# Ethernet1.net
KiCad netlist of a schematic drawn in Altium Designer
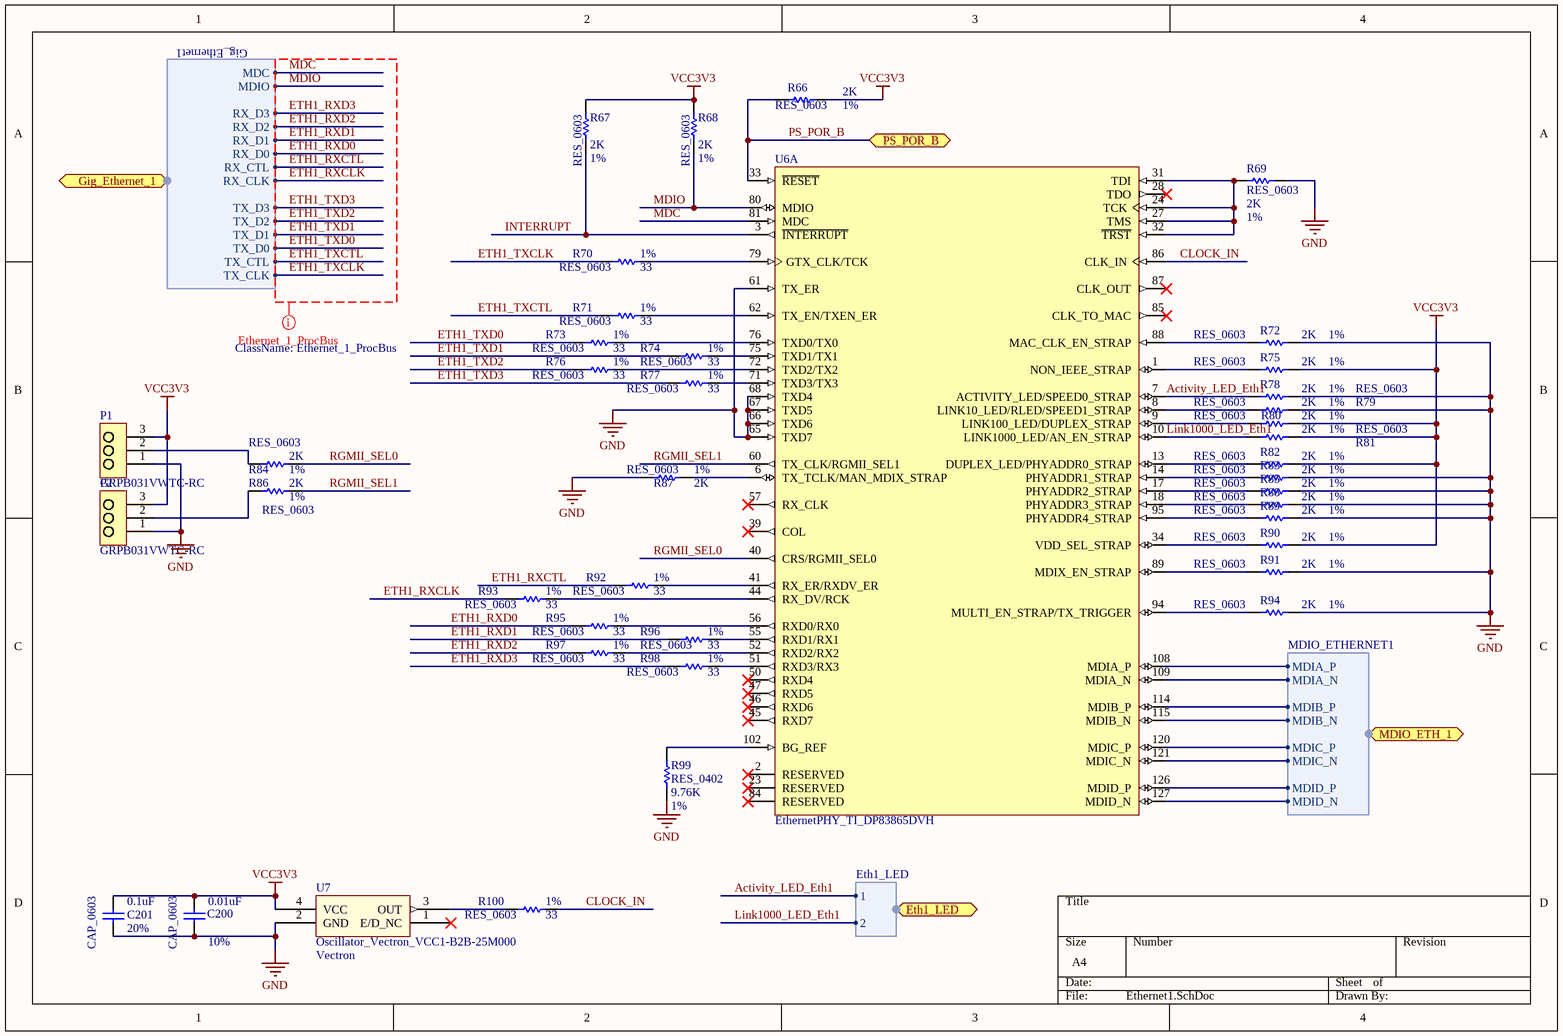
[diagram p0: Ethernet1.SchDoc]

(export (version "E")
  (design (tool "Eeschema 10.0.6"))
  (components
    (comp (ref "C200")
      (value "CAP_0603")
      (footprint "CAPC0603(1608)100_N")
      (description "CAP CER 10000PF 6.3V X7R 0603")
      (fields
        (field (name "ALTIUM_VALUE") "0.01uF")
        (field (name "TOLERANCE") "10%")
        (field (name "PART NUMBER") "C0603C103K9RACTU")
        (field (name "MANUFACTURER") "Kemet")
      )
      (libsource (lib "COMRAD_Database") (part "CAP_0603"))
    )
    (comp (ref "C201")
      (value "CAP_0603")
      (footprint "CAPC0603(1608)100_N")
      (description "CAP CER 0.1UF 6.3V 20% X7R 0603")
      (fields
        (field (name "ALTIUM_VALUE") "0.1uF")
        (field (name "TOLERANCE") "20%")
        (field (name "PART NUMBER") "6R3X14W104MV4T")
        (field (name "MANUFACTURER") "Johanson Dielectrics Inc")
      )
      (libsource (lib "COMRAD_Database") (part "CAP_0603"))
    )
    (comp (ref "P1")
      (value "GRPB031VWTC-RC")
      (footprint "Header_3-Pos_Sullins_GRPB031VWTC-RC")
      (description "CONN HEADER .050\" 3POS SMD GOLD")
      (fields (field (name "MANUFACTURER") "Sullins Connector Solutions"))
      (libsource (lib "COMRAD_Database") (part "Jumper_Header3"))
    )
    (comp (ref "P2")
      (value "GRPB031VWTC-RC")
      (footprint "Header_3-Pos_Sullins_GRPB031VWTC-RC")
      (description "CONN HEADER .050\" 3POS SMD GOLD")
      (fields (field (name "MANUFACTURER") "Sullins Connector Solutions"))
      (libsource (lib "COMRAD_Database") (part "Jumper_Header3"))
    )
    (comp (ref "R66")
      (value "RES_0603")
      (footprint "RESC0603(1608)_N")
      (description "RES 2.00K OHM 1/10W 1% 0603 SMD")
      (fields
        (field (name "ALTIUM_VALUE") "2K")
        (field (name "TOLERANCE") "1%")
        (field (name "PART NUMBER") "ERJ-3EKF2001V")
        (field (name "MANUFACTURER") "Panasonic Electronics Components")
      )
      (libsource (lib "COMRAD_Database") (part "RES_0603"))
    )
    (comp (ref "R67")
      (value "RES_0603")
      (footprint "RESC0603(1608)_N")
      (description "RES 2.00K OHM 1/10W 1% 0603 SMD")
      (fields
        (field (name "ALTIUM_VALUE") "2K")
        (field (name "TOLERANCE") "1%")
        (field (name "PART NUMBER") "ERJ-3EKF2001V")
        (field (name "MANUFACTURER") "Panasonic Electronics Components")
      )
      (libsource (lib "COMRAD_Database") (part "RES_0603"))
    )
    (comp (ref "R68")
      (value "RES_0603")
      (footprint "RESC0603(1608)_N")
      (description "RES 2.00K OHM 1/10W 1% 0603 SMD")
      (fields
        (field (name "ALTIUM_VALUE") "2K")
        (field (name "TOLERANCE") "1%")
        (field (name "PART NUMBER") "ERJ-3EKF2001V")
        (field (name "MANUFACTURER") "Panasonic Electronics Components")
      )
      (libsource (lib "COMRAD_Database") (part "RES_0603"))
    )
    (comp (ref "R69")
      (value "RES_0603")
      (footprint "RESC0603(1608)_N")
      (description "RES 2.00K OHM 1/10W 1% 0603 SMD")
      (fields
        (field (name "ALTIUM_VALUE") "2K")
        (field (name "TOLERANCE") "1%")
        (field (name "PART NUMBER") "ERJ-3EKF2001V")
        (field (name "MANUFACTURER") "Panasonic Electronics Components")
      )
      (libsource (lib "COMRAD_Database") (part "RES_0603"))
    )
    (comp (ref "R70")
      (value "RES_0603")
      (footprint "RESC0603(1608)_N")
      (description "RES 33.0 OHM 1/10W 1% 0603 SMD")
      (fields
        (field (name "ALTIUM_VALUE") "33")
        (field (name "TOLERANCE") "1%")
        (field (name "PART NUMBER") "ERJ-3EKF33R0V")
        (field (name "MANUFACTURER") "Panasonic Electronics Components")
      )
      (libsource (lib "COMRAD_Database") (part "RES_0603"))
    )
    (comp (ref "R71")
      (value "RES_0603")
      (footprint "RESC0603(1608)_N")
      (description "RES 33.0 OHM 1/10W 1% 0603 SMD")
      (fields
        (field (name "ALTIUM_VALUE") "33")
        (field (name "TOLERANCE") "1%")
        (field (name "PART NUMBER") "ERJ-3EKF33R0V")
        (field (name "MANUFACTURER") "Panasonic Electronics Components")
      )
      (libsource (lib "COMRAD_Database") (part "RES_0603"))
    )
    (comp (ref "R72")
      (value "RES_0603")
      (footprint "RESC0603(1608)_N")
      (description "RES 2.00K OHM 1/10W 1% 0603 SMD")
      (fields
        (field (name "ALTIUM_VALUE") "2K")
        (field (name "TOLERANCE") "1%")
        (field (name "PART NUMBER") "ERJ-3EKF2001V")
        (field (name "MANUFACTURER") "Panasonic Electronics Components")
      )
      (libsource (lib "COMRAD_Database") (part "RES_0603"))
    )
    (comp (ref "R73")
      (value "RES_0603")
      (footprint "RESC0603(1608)_N")
      (description "RES 33.0 OHM 1/10W 1% 0603 SMD")
      (fields
        (field (name "ALTIUM_VALUE") "33")
        (field (name "TOLERANCE") "1%")
        (field (name "PART NUMBER") "ERJ-3EKF33R0V")
        (field (name "MANUFACTURER") "Panasonic Electronics Components")
      )
      (libsource (lib "COMRAD_Database") (part "RES_0603"))
    )
    (comp (ref "R74")
      (value "RES_0603")
      (footprint "RESC0603(1608)_N")
      (description "RES 33.0 OHM 1/10W 1% 0603 SMD")
      (fields
        (field (name "ALTIUM_VALUE") "33")
        (field (name "TOLERANCE") "1%")
        (field (name "PART NUMBER") "ERJ-3EKF33R0V")
        (field (name "MANUFACTURER") "Panasonic Electronics Components")
      )
      (libsource (lib "COMRAD_Database") (part "RES_0603"))
    )
    (comp (ref "R75")
      (value "RES_0603")
      (footprint "RESC0603(1608)_N")
      (description "RES 2.00K OHM 1/10W 1% 0603 SMD")
      (fields
        (field (name "ALTIUM_VALUE") "2K")
        (field (name "TOLERANCE") "1%")
        (field (name "PART NUMBER") "ERJ-3EKF2001V")
        (field (name "MANUFACTURER") "Panasonic Electronics Components")
      )
      (libsource (lib "COMRAD_Database") (part "RES_0603"))
    )
    (comp (ref "R76")
      (value "RES_0603")
      (footprint "RESC0603(1608)_N")
      (description "RES 33.0 OHM 1/10W 1% 0603 SMD")
      (fields
        (field (name "ALTIUM_VALUE") "33")
        (field (name "TOLERANCE") "1%")
        (field (name "PART NUMBER") "ERJ-3EKF33R0V")
        (field (name "MANUFACTURER") "Panasonic Electronics Components")
      )
      (libsource (lib "COMRAD_Database") (part "RES_0603"))
    )
    (comp (ref "R77")
      (value "RES_0603")
      (footprint "RESC0603(1608)_N")
      (description "RES 33.0 OHM 1/10W 1% 0603 SMD")
      (fields
        (field (name "ALTIUM_VALUE") "33")
        (field (name "TOLERANCE") "1%")
        (field (name "PART NUMBER") "ERJ-3EKF33R0V")
        (field (name "MANUFACTURER") "Panasonic Electronics Components")
      )
      (libsource (lib "COMRAD_Database") (part "RES_0603"))
    )
    (comp (ref "R78")
      (value "RES_0603")
      (footprint "RESC0603(1608)_N")
      (description "RES 2.00K OHM 1/10W 1% 0603 SMD")
      (fields
        (field (name "ALTIUM_VALUE") "2K")
        (field (name "TOLERANCE") "1%")
        (field (name "PART NUMBER") "ERJ-3EKF2001V")
        (field (name "MANUFACTURER") "Panasonic Electronics Components")
      )
      (libsource (lib "COMRAD_Database") (part "RES_0603"))
    )
    (comp (ref "R79")
      (value "RES_0603")
      (footprint "RESC0603(1608)_N")
      (description "RES 2.00K OHM 1/10W 1% 0603 SMD")
      (fields
        (field (name "ALTIUM_VALUE") "2K")
        (field (name "TOLERANCE") "1%")
        (field (name "PART NUMBER") "ERJ-3EKF2001V")
        (field (name "MANUFACTURER") "Panasonic Electronics Components")
      )
      (libsource (lib "COMRAD_Database") (part "RES_0603"))
    )
    (comp (ref "R80")
      (value "RES_0603")
      (footprint "RESC0603(1608)_N")
      (description "RES 2.00K OHM 1/10W 1% 0603 SMD")
      (fields
        (field (name "ALTIUM_VALUE") "2K")
        (field (name "TOLERANCE") "1%")
        (field (name "PART NUMBER") "ERJ-3EKF2001V")
        (field (name "MANUFACTURER") "Panasonic Electronics Components")
      )
      (libsource (lib "COMRAD_Database") (part "RES_0603"))
    )
    (comp (ref "R81")
      (value "RES_0603")
      (footprint "RESC0603(1608)_N")
      (description "RES 2.00K OHM 1/10W 1% 0603 SMD")
      (fields
        (field (name "ALTIUM_VALUE") "2K")
        (field (name "TOLERANCE") "1%")
        (field (name "PART NUMBER") "ERJ-3EKF2001V")
        (field (name "MANUFACTURER") "Panasonic Electronics Components")
      )
      (libsource (lib "COMRAD_Database") (part "RES_0603"))
    )
    (comp (ref "R82")
      (value "RES_0603")
      (footprint "RESC0603(1608)_N")
      (description "RES 2.00K OHM 1/10W 1% 0603 SMD")
      (fields
        (field (name "ALTIUM_VALUE") "2K")
        (field (name "TOLERANCE") "1%")
        (field (name "PART NUMBER") "ERJ-3EKF2001V")
        (field (name "MANUFACTURER") "Panasonic Electronics Components")
      )
      (libsource (lib "COMRAD_Database") (part "RES_0603"))
    )
    (comp (ref "R83")
      (value "RES_0603")
      (footprint "RESC0603(1608)_N")
      (description "RES 2.00K OHM 1/10W 1% 0603 SMD")
      (fields
        (field (name "ALTIUM_VALUE") "2K")
        (field (name "TOLERANCE") "1%")
        (field (name "PART NUMBER") "ERJ-3EKF2001V")
        (field (name "MANUFACTURER") "Panasonic Electronics Components")
      )
      (libsource (lib "COMRAD_Database") (part "RES_0603"))
    )
    (comp (ref "R84")
      (value "RES_0603")
      (footprint "RESC0603(1608)_N")
      (description "RES 2.00K OHM 1/10W 1% 0603 SMD")
      (fields
        (field (name "ALTIUM_VALUE") "2K")
        (field (name "TOLERANCE") "1%")
        (field (name "PART NUMBER") "ERJ-3EKF2001V")
        (field (name "MANUFACTURER") "Panasonic Electronics Components")
      )
      (libsource (lib "COMRAD_Database") (part "RES_0603"))
    )
    (comp (ref "R85")
      (value "RES_0603")
      (footprint "RESC0603(1608)_N")
      (description "RES 2.00K OHM 1/10W 1% 0603 SMD")
      (fields
        (field (name "ALTIUM_VALUE") "2K")
        (field (name "TOLERANCE") "1%")
        (field (name "PART NUMBER") "ERJ-3EKF2001V")
        (field (name "MANUFACTURER") "Panasonic Electronics Components")
      )
      (libsource (lib "COMRAD_Database") (part "RES_0603"))
    )
    (comp (ref "R86")
      (value "RES_0603")
      (footprint "RESC0603(1608)_N")
      (description "RES 2.00K OHM 1/10W 1% 0603 SMD")
      (fields
        (field (name "ALTIUM_VALUE") "2K")
        (field (name "TOLERANCE") "1%")
        (field (name "PART NUMBER") "ERJ-3EKF2001V")
        (field (name "MANUFACTURER") "Panasonic Electronics Components")
      )
      (libsource (lib "COMRAD_Database") (part "RES_0603"))
    )
    (comp (ref "R87")
      (value "RES_0603")
      (footprint "RESC0603(1608)_N")
      (description "RES 2.00K OHM 1/10W 1% 0603 SMD")
      (fields
        (field (name "ALTIUM_VALUE") "2K")
        (field (name "TOLERANCE") "1%")
        (field (name "PART NUMBER") "ERJ-3EKF2001V")
        (field (name "MANUFACTURER") "Panasonic Electronics Components")
      )
      (libsource (lib "COMRAD_Database") (part "RES_0603"))
    )
    (comp (ref "R88")
      (value "RES_0603")
      (footprint "RESC0603(1608)_N")
      (description "RES 2.00K OHM 1/10W 1% 0603 SMD")
      (fields
        (field (name "ALTIUM_VALUE") "2K")
        (field (name "TOLERANCE") "1%")
        (field (name "PART NUMBER") "ERJ-3EKF2001V")
        (field (name "MANUFACTURER") "Panasonic Electronics Components")
      )
      (libsource (lib "COMRAD_Database") (part "RES_0603"))
    )
    (comp (ref "R89")
      (value "RES_0603")
      (footprint "RESC0603(1608)_N")
      (description "RES 2.00K OHM 1/10W 1% 0603 SMD")
      (fields
        (field (name "ALTIUM_VALUE") "2K")
        (field (name "TOLERANCE") "1%")
        (field (name "PART NUMBER") "ERJ-3EKF2001V")
        (field (name "MANUFACTURER") "Panasonic Electronics Components")
      )
      (libsource (lib "COMRAD_Database") (part "RES_0603"))
    )
    (comp (ref "R90")
      (value "RES_0603")
      (footprint "RESC0603(1608)_N")
      (description "RES 2.00K OHM 1/10W 1% 0603 SMD")
      (fields
        (field (name "ALTIUM_VALUE") "2K")
        (field (name "TOLERANCE") "1%")
        (field (name "PART NUMBER") "ERJ-3EKF2001V")
        (field (name "MANUFACTURER") "Panasonic Electronics Components")
      )
      (libsource (lib "COMRAD_Database") (part "RES_0603"))
    )
    (comp (ref "R91")
      (value "RES_0603")
      (footprint "RESC0603(1608)_N")
      (description "RES 2.00K OHM 1/10W 1% 0603 SMD")
      (fields
        (field (name "ALTIUM_VALUE") "2K")
        (field (name "TOLERANCE") "1%")
        (field (name "PART NUMBER") "ERJ-3EKF2001V")
        (field (name "MANUFACTURER") "Panasonic Electronics Components")
      )
      (libsource (lib "COMRAD_Database") (part "RES_0603"))
    )
    (comp (ref "R92")
      (value "RES_0603")
      (footprint "RESC0603(1608)_N")
      (description "RES 33.0 OHM 1/10W 1% 0603 SMD")
      (fields
        (field (name "ALTIUM_VALUE") "33")
        (field (name "TOLERANCE") "1%")
        (field (name "PART NUMBER") "ERJ-3EKF33R0V")
        (field (name "MANUFACTURER") "Panasonic Electronics Components")
      )
      (libsource (lib "COMRAD_Database") (part "RES_0603"))
    )
    (comp (ref "R93")
      (value "RES_0603")
      (footprint "RESC0603(1608)_N")
      (description "RES 33.0 OHM 1/10W 1% 0603 SMD")
      (fields
        (field (name "ALTIUM_VALUE") "33")
        (field (name "TOLERANCE") "1%")
        (field (name "PART NUMBER") "ERJ-3EKF33R0V")
        (field (name "MANUFACTURER") "Panasonic Electronics Components")
      )
      (libsource (lib "COMRAD_Database") (part "RES_0603"))
    )
    (comp (ref "R94")
      (value "RES_0603")
      (footprint "RESC0603(1608)_N")
      (description "RES 2.00K OHM 1/10W 1% 0603 SMD")
      (fields
        (field (name "ALTIUM_VALUE") "2K")
        (field (name "TOLERANCE") "1%")
        (field (name "PART NUMBER") "ERJ-3EKF2001V")
        (field (name "MANUFACTURER") "Panasonic Electronics Components")
      )
      (libsource (lib "COMRAD_Database") (part "RES_0603"))
    )
    (comp (ref "R95")
      (value "RES_0603")
      (footprint "RESC0603(1608)_N")
      (description "RES 33.0 OHM 1/10W 1% 0603 SMD")
      (fields
        (field (name "ALTIUM_VALUE") "33")
        (field (name "TOLERANCE") "1%")
        (field (name "PART NUMBER") "ERJ-3EKF33R0V")
        (field (name "MANUFACTURER") "Panasonic Electronics Components")
      )
      (libsource (lib "COMRAD_Database") (part "RES_0603"))
    )
    (comp (ref "R96")
      (value "RES_0603")
      (footprint "RESC0603(1608)_N")
      (description "RES 33.0 OHM 1/10W 1% 0603 SMD")
      (fields
        (field (name "ALTIUM_VALUE") "33")
        (field (name "TOLERANCE") "1%")
        (field (name "PART NUMBER") "ERJ-3EKF33R0V")
        (field (name "MANUFACTURER") "Panasonic Electronics Components")
      )
      (libsource (lib "COMRAD_Database") (part "RES_0603"))
    )
    (comp (ref "R97")
      (value "RES_0603")
      (footprint "RESC0603(1608)_N")
      (description "RES 33.0 OHM 1/10W 1% 0603 SMD")
      (fields
        (field (name "ALTIUM_VALUE") "33")
        (field (name "TOLERANCE") "1%")
        (field (name "PART NUMBER") "ERJ-3EKF33R0V")
        (field (name "MANUFACTURER") "Panasonic Electronics Components")
      )
      (libsource (lib "COMRAD_Database") (part "RES_0603"))
    )
    (comp (ref "R98")
      (value "RES_0603")
      (footprint "RESC0603(1608)_N")
      (description "RES 33.0 OHM 1/10W 1% 0603 SMD")
      (fields
        (field (name "ALTIUM_VALUE") "33")
        (field (name "TOLERANCE") "1%")
        (field (name "PART NUMBER") "ERJ-3EKF33R0V")
        (field (name "MANUFACTURER") "Panasonic Electronics Components")
      )
      (libsource (lib "COMRAD_Database") (part "RES_0603"))
    )
    (comp (ref "R99")
      (value "RES_0402")
      (footprint "RESC0402(1005)_N")
      (description "9.76K ohm, 1% 1/16W, 0402")
      (fields
        (field (name "ALTIUM_VALUE") "9.76K")
        (field (name "TOLERANCE") "1%")
        (field (name "PART NUMBER") "CRCW04029K76FKED")
        (field (name "MANUFACTURER") "Vishay/Dale")
      )
      (libsource (lib "COMRAD_Database") (part "RES_0402"))
    )
    (comp (ref "R100")
      (value "RES_0603")
      (footprint "RESC0603(1608)_N")
      (description "RES 33.0 OHM 1/10W 1% 0603 SMD")
      (fields
        (field (name "ALTIUM_VALUE") "33")
        (field (name "TOLERANCE") "1%")
        (field (name "PART NUMBER") "ERJ-3EKF33R0V")
        (field (name "MANUFACTURER") "Panasonic Electronics Components")
      )
      (libsource (lib "COMRAD_Database") (part "RES_0603"))
    )
    (comp (ref "U6")
      (value "EthernetPHY_TI_DP83865DVH")
      (footprint "EthernetPHY_TI_DP83865(PQFP)_VLA128A_N")
      (description "Ethernet PHY_TI_DP83865DVH, Gigabit Ethernet PHYTER,128 Lead Plastic Flat Pack")
      (fields (field (name "PART NUMBER") "DP83865DVH") (field (name "MANUFACTURER") "Texas Instruments"))
      (libsource (lib "COMRAD_Database") (part "EthernetPHY_TI_DP83865DVH"))
    )
    (comp (ref "U7")
      (value "Oscillator_Vectron_VCC1-B2B-25M000")
      (footprint "Oscillator_Vectron_VCC1-B2B-25M000_SMD")
      (description "VCC1-B2B-25M000, 25MHz, 3.3V +/- 10%, No tri-state, +/-50 ppm, -40 to +85 deg")
      (fields (field (name "PART NUMBER") "VCC1-B2B-25M000") (field (name "MANUFACTURER") "Vectron"))
      (libsource (lib "COMRAD_Database") (part "Oscillator_Vectron_VCC1-B2B-25M000"))
    )
  )
  (nets
    (net (code "4") (name "/Activity_LED_Eth1") (class "Default")
      (node (ref "R78") (pin "2") (pinfunction "2_2") (pintype "passive"))
      (node (ref "U6") (pin "7") (pinfunction "ACTIVITY_LED/SPEED0_STRAP_7") (pintype "bidirectional"))
    )
    (net (code "5") (name "/CLOCK_IN") (class "Default")
      (node (ref "R100") (pin "2") (pinfunction "2_2") (pintype "passive"))
      (node (ref "U6") (pin "86") (pinfunction "CLK_IN_86") (pintype "input"))
    )
    (net (code "6") (name "/ETH1_RXCLK") (class "Default")
      (node (ref "R93") (pin "1") (pinfunction "1_1") (pintype "passive"))
    )
    (net (code "7") (name "/ETH1_RXCTL") (class "Default")
      (node (ref "R92") (pin "1") (pinfunction "1_1") (pintype "passive"))
    )
    (net (code "8") (name "/ETH1_RXD0") (class "Default")
      (node (ref "R95") (pin "1") (pinfunction "1_1") (pintype "passive"))
    )
    (net (code "9") (name "/ETH1_RXD1") (class "Default")
      (node (ref "R96") (pin "1") (pinfunction "1_1") (pintype "passive"))
    )
    (net (code "10") (name "/ETH1_RXD2") (class "Default")
      (node (ref "R97") (pin "1") (pinfunction "1_1") (pintype "passive"))
    )
    (net (code "11") (name "/ETH1_RXD3") (class "Default")
      (node (ref "R98") (pin "1") (pinfunction "1_1") (pintype "passive"))
    )
    (net (code "12") (name "/ETH1_TXCLK") (class "Default")
      (node (ref "R70") (pin "1") (pinfunction "1_1") (pintype "passive"))
    )
    (net (code "13") (name "/ETH1_TXCTL") (class "Default")
      (node (ref "R71") (pin "1") (pinfunction "1_1") (pintype "passive"))
    )
    (net (code "14") (name "/ETH1_TXD0") (class "Default")
      (node (ref "R73") (pin "1") (pinfunction "1_1") (pintype "passive"))
    )
    (net (code "15") (name "/ETH1_TXD1") (class "Default")
      (node (ref "R74") (pin "1") (pinfunction "1_1") (pintype "passive"))
    )
    (net (code "16") (name "/ETH1_TXD2") (class "Default")
      (node (ref "R76") (pin "1") (pinfunction "1_1") (pintype "passive"))
    )
    (net (code "17") (name "/ETH1_TXD3") (class "Default")
      (node (ref "R77") (pin "1") (pinfunction "1_1") (pintype "passive"))
    )
    (net (code "18") (name "/INTERRUPT") (class "Default")
      (node (ref "R67") (pin "1") (pinfunction "1_1") (pintype "passive"))
      (node (ref "U6") (pin "3") (pinfunction "~{INTERRUPT}_3") (pintype "output"))
    )
    (net (code "19") (name "/Link1000_LED_Eth1") (class "Default")
      (node (ref "R81") (pin "2") (pinfunction "2_2") (pintype "passive"))
      (node (ref "U6") (pin "10") (pinfunction "LINK1000_LED/AN_EN_STRAP_10") (pintype "bidirectional"))
    )
    (net (code "20") (name "/MDC") (class "Default")
      (node (ref "U6") (pin "81") (pinfunction "MDC_81") (pintype "input"))
    )
    (net (code "21") (name "/MDIA_N") (class "Default")
      (node (ref "U6") (pin "109") (pinfunction "MDIA_N_109") (pintype "bidirectional"))
    )
    (net (code "22") (name "/MDIA_P") (class "Default")
      (node (ref "U6") (pin "108") (pinfunction "MDIA_P_108") (pintype "bidirectional"))
    )
    (net (code "23") (name "/MDIB_N") (class "Default")
      (node (ref "U6") (pin "115") (pinfunction "MDIB_N_115") (pintype "bidirectional"))
    )
    (net (code "24") (name "/MDIB_P") (class "Default")
      (node (ref "U6") (pin "114") (pinfunction "MDIB_P_114") (pintype "bidirectional"))
    )
    (net (code "25") (name "/MDIC_N") (class "Default")
      (node (ref "U6") (pin "121") (pinfunction "MDIC_N_121") (pintype "bidirectional"))
    )
    (net (code "26") (name "/MDIC_P") (class "Default")
      (node (ref "U6") (pin "120") (pinfunction "MDIC_P_120") (pintype "bidirectional"))
    )
    (net (code "27") (name "/MDID_N") (class "Default")
      (node (ref "U6") (pin "127") (pinfunction "MDID_N_127") (pintype "bidirectional"))
    )
    (net (code "28") (name "/MDID_P") (class "Default")
      (node (ref "U6") (pin "126") (pinfunction "MDID_P_126") (pintype "bidirectional"))
    )
    (net (code "29") (name "/MDIO") (class "Default")
      (node (ref "R68") (pin "1") (pinfunction "1_1") (pintype "passive"))
      (node (ref "U6") (pin "80") (pinfunction "MDIO_80") (pintype "bidirectional"))
    )
    (net (code "30") (name "/PS_POR_B") (class "Default")
      (node (ref "R66") (pin "2") (pinfunction "2_2") (pintype "passive"))
      (node (ref "U6") (pin "33") (pinfunction "~{RESET}_33") (pintype "input"))
    )
    (net (code "31") (name "/RGMII_SEL0") (class "Default")
      (node (ref "R84") (pin "1") (pinfunction "1_1") (pintype "passive"))
      (node (ref "U6") (pin "40") (pinfunction "CRS/RGMII_SEL0_40") (pintype "output"))
    )
    (net (code "32") (name "/RGMII_SEL1") (class "Default")
      (node (ref "R86") (pin "1") (pinfunction "1_1") (pintype "passive"))
      (node (ref "U6") (pin "60") (pinfunction "TX_CLK/RGMII_SEL1_60") (pintype "output"))
    )
    (net (code "36") (name "GND") (class "Default")
      (node (ref "C200") (pin "1") (pinfunction "1_1") (pintype "passive"))
      (node (ref "C201") (pin "2") (pinfunction "2_2") (pintype "passive"))
      (node (ref "P1") (pin "1") (pinfunction "1_1") (pintype "passive"))
      (node (ref "P2") (pin "1") (pinfunction "1_1") (pintype "passive"))
      (node (ref "R69") (pin "1") (pinfunction "1_1") (pintype "passive"))
      (node (ref "R72") (pin "1") (pinfunction "1_1") (pintype "passive"))
      (node (ref "R78") (pin "1") (pinfunction "1_1") (pintype "passive"))
      (node (ref "R79") (pin "1") (pinfunction "1_1") (pintype "passive"))
      (node (ref "R83") (pin "1") (pinfunction "1_1") (pintype "passive"))
      (node (ref "R85") (pin "1") (pinfunction "1_1") (pintype "passive"))
      (node (ref "R87") (pin "2") (pinfunction "2_2") (pintype "passive"))
      (node (ref "R88") (pin "1") (pinfunction "1_1") (pintype "passive"))
      (node (ref "R89") (pin "1") (pinfunction "1_1") (pintype "passive"))
      (node (ref "R91") (pin "1") (pinfunction "1_1") (pintype "passive"))
      (node (ref "R94") (pin "1") (pinfunction "1_1") (pintype "passive"))
      (node (ref "R99") (pin "1") (pinfunction "1_1") (pintype "passive"))
      (node (ref "U6") (pin "61") (pinfunction "TX_ER_61") (pintype "input"))
      (node (ref "U6") (pin "65") (pinfunction "TXD7_65") (pintype "input"))
      (node (ref "U6") (pin "66") (pinfunction "TXD6_66") (pintype "input"))
      (node (ref "U6") (pin "67") (pinfunction "TXD5_67") (pintype "input"))
      (node (ref "U6") (pin "68") (pinfunction "TXD4_68") (pintype "input"))
      (node (ref "U7") (pin "2") (pinfunction "GND_2") (pintype "power_in"))
    )
    (net (code "37") (name "Net-(P1-Pad2)") (class "Default")
      (node (ref "P1") (pin "2") (pinfunction "2_2") (pintype "passive"))
      (node (ref "R84") (pin "2") (pinfunction "2_2") (pintype "passive"))
    )
    (net (code "38") (name "Net-(P2-Pad2)") (class "Default")
      (node (ref "P2") (pin "2") (pinfunction "2_2") (pintype "passive"))
      (node (ref "R86") (pin "2") (pinfunction "2_2") (pintype "passive"))
    )
    (net (code "39") (name "Net-(U6A-BG_REF)") (class "Default")
      (node (ref "R99") (pin "2") (pinfunction "2_2") (pintype "passive"))
      (node (ref "U6") (pin "102") (pinfunction "BG_REF_102") (pintype "input"))
    )
    (net (code "40") (name "Net-(U6A-DUPLEX_LED{slash}PHYADDR0_STRAP)") (class "Default")
      (node (ref "R82") (pin "2") (pinfunction "2_2") (pintype "passive"))
      (node (ref "U6") (pin "13") (pinfunction "DUPLEX_LED/PHYADDR0_STRAP_13") (pintype "bidirectional"))
    )
    (net (code "41") (name "Net-(U6A-GTX_CLK{slash}TCK)") (class "Default")
      (node (ref "R70") (pin "2") (pinfunction "2_2") (pintype "passive"))
      (node (ref "U6") (pin "79") (pinfunction "GTX_CLK/TCK_79") (pintype "input"))
    )
    (net (code "42") (name "Net-(U6A-LINK10_LED{slash}RLED{slash}SPEED1_STRAP)") (class "Default")
      (node (ref "R79") (pin "2") (pinfunction "2_2") (pintype "passive"))
      (node (ref "U6") (pin "8") (pinfunction "LINK10_LED/RLED/SPEED1_STRAP_8") (pintype "bidirectional"))
    )
    (net (code "43") (name "Net-(U6A-LINK100_LED{slash}DUPLEX_STRAP)") (class "Default")
      (node (ref "R80") (pin "2") (pinfunction "2_2") (pintype "passive"))
      (node (ref "U6") (pin "9") (pinfunction "LINK100_LED/DUPLEX_STRAP_9") (pintype "bidirectional"))
    )
    (net (code "44") (name "Net-(U6A-MAC_CLK_EN_STRAP)") (class "Default")
      (node (ref "R72") (pin "2") (pinfunction "2_2") (pintype "passive"))
      (node (ref "U6") (pin "88") (pinfunction "MAC_CLK_EN_STRAP_88") (pintype "input"))
    )
    (net (code "45") (name "Net-(U6A-MDIX_EN_STRAP)") (class "Default")
      (node (ref "R91") (pin "2") (pinfunction "2_2") (pintype "passive"))
      (node (ref "U6") (pin "89") (pinfunction "MDIX_EN_STRAP_89") (pintype "bidirectional"))
    )
    (net (code "46") (name "Net-(U6A-MULTI_EN_STRAP{slash}TX_TRIGGER)") (class "Default")
      (node (ref "R94") (pin "2") (pinfunction "2_2") (pintype "passive"))
      (node (ref "U6") (pin "94") (pinfunction "MULTI_EN_STRAP/TX_TRIGGER_94") (pintype "bidirectional"))
    )
    (net (code "47") (name "Net-(U6A-NON_IEEE_STRAP)") (class "Default")
      (node (ref "R75") (pin "2") (pinfunction "2_2") (pintype "passive"))
      (node (ref "U6") (pin "1") (pinfunction "NON_IEEE_STRAP_1") (pintype "bidirectional"))
    )
    (net (code "48") (name "Net-(U6A-PHYADDR1_STRAP)") (class "Default")
      (node (ref "R83") (pin "2") (pinfunction "2_2") (pintype "passive"))
      (node (ref "U6") (pin "14") (pinfunction "PHYADDR1_STRAP_14") (pintype "input"))
    )
    (net (code "49") (name "Net-(U6A-PHYADDR2_STRAP)") (class "Default")
      (node (ref "R85") (pin "2") (pinfunction "2_2") (pintype "passive"))
      (node (ref "U6") (pin "17") (pinfunction "PHYADDR2_STRAP_17") (pintype "input"))
    )
    (net (code "50") (name "Net-(U6A-PHYADDR3_STRAP)") (class "Default")
      (node (ref "R88") (pin "2") (pinfunction "2_2") (pintype "passive"))
      (node (ref "U6") (pin "18") (pinfunction "PHYADDR3_STRAP_18") (pintype "input"))
    )
    (net (code "51") (name "Net-(U6A-PHYADDR4_STRAP)") (class "Default")
      (node (ref "R89") (pin "2") (pinfunction "2_2") (pintype "passive"))
      (node (ref "U6") (pin "95") (pinfunction "PHYADDR4_STRAP_95") (pintype "input"))
    )
    (net (code "52") (name "Net-(U6A-RXD0{slash}RX0)") (class "Default")
      (node (ref "R95") (pin "2") (pinfunction "2_2") (pintype "passive"))
      (node (ref "U6") (pin "56") (pinfunction "RXD0/RX0_56") (pintype "output"))
    )
    (net (code "53") (name "Net-(U6A-RXD1{slash}RX1)") (class "Default")
      (node (ref "R96") (pin "2") (pinfunction "2_2") (pintype "passive"))
      (node (ref "U6") (pin "55") (pinfunction "RXD1/RX1_55") (pintype "output"))
    )
    (net (code "54") (name "Net-(U6A-RXD2{slash}RX2)") (class "Default")
      (node (ref "R97") (pin "2") (pinfunction "2_2") (pintype "passive"))
      (node (ref "U6") (pin "52") (pinfunction "RXD2/RX2_52") (pintype "output"))
    )
    (net (code "55") (name "Net-(U6A-RXD3{slash}RX3)") (class "Default")
      (node (ref "R98") (pin "2") (pinfunction "2_2") (pintype "passive"))
      (node (ref "U6") (pin "51") (pinfunction "RXD3/RX3_51") (pintype "output"))
    )
    (net (code "56") (name "Net-(U6A-RX_DV{slash}RCK)") (class "Default")
      (node (ref "R93") (pin "2") (pinfunction "2_2") (pintype "passive"))
      (node (ref "U6") (pin "44") (pinfunction "RX_DV/RCK_44") (pintype "output"))
    )
    (net (code "57") (name "Net-(U6A-RX_ER{slash}RXDV_ER)") (class "Default")
      (node (ref "R92") (pin "2") (pinfunction "2_2") (pintype "passive"))
      (node (ref "U6") (pin "41") (pinfunction "RX_ER/RXDV_ER_41") (pintype "output"))
    )
    (net (code "58") (name "Net-(U6A-TCK)") (class "Default")
      (node (ref "R69") (pin "2") (pinfunction "2_2") (pintype "passive"))
      (node (ref "U6") (pin "24") (pinfunction "TCK_24") (pintype "input"))
      (node (ref "U6") (pin "27") (pinfunction "TMS_27") (pintype "input"))
      (node (ref "U6") (pin "31") (pinfunction "TDI_31") (pintype "input"))
      (node (ref "U6") (pin "32") (pinfunction "~{TRST}_32") (pintype "input"))
    )
    (net (code "59") (name "Net-(U6A-TXD0{slash}TX0)") (class "Default")
      (node (ref "R73") (pin "2") (pinfunction "2_2") (pintype "passive"))
      (node (ref "U6") (pin "76") (pinfunction "TXD0/TX0_76") (pintype "input"))
    )
    (net (code "60") (name "Net-(U6A-TXD1{slash}TX1)") (class "Default")
      (node (ref "R74") (pin "2") (pinfunction "2_2") (pintype "passive"))
      (node (ref "U6") (pin "75") (pinfunction "TXD1/TX1_75") (pintype "input"))
    )
    (net (code "61") (name "Net-(U6A-TXD2{slash}TX2)") (class "Default")
      (node (ref "R76") (pin "2") (pinfunction "2_2") (pintype "passive"))
      (node (ref "U6") (pin "72") (pinfunction "TXD2/TX2_72") (pintype "input"))
    )
    (net (code "62") (name "Net-(U6A-TXD3{slash}TX3)") (class "Default")
      (node (ref "R77") (pin "2") (pinfunction "2_2") (pintype "passive"))
      (node (ref "U6") (pin "71") (pinfunction "TXD3/TX3_71") (pintype "input"))
    )
    (net (code "63") (name "Net-(U6A-TX_EN{slash}TXEN_ER)") (class "Default")
      (node (ref "R71") (pin "2") (pinfunction "2_2") (pintype "passive"))
      (node (ref "U6") (pin "62") (pinfunction "TX_EN/TXEN_ER_62") (pintype "input"))
    )
    (net (code "64") (name "Net-(U6A-TX_TCLK{slash}MAN_MDIX_STRAP)") (class "Default")
      (node (ref "R87") (pin "1") (pinfunction "1_1") (pintype "passive"))
      (node (ref "U6") (pin "6") (pinfunction "TX_TCLK/MAN_MDIX_STRAP_6") (pintype "bidirectional"))
    )
    (net (code "65") (name "Net-(U6A-VDD_SEL_STRAP)") (class "Default")
      (node (ref "R90") (pin "2") (pinfunction "2_2") (pintype "passive"))
      (node (ref "U6") (pin "34") (pinfunction "VDD_SEL_STRAP_34") (pintype "bidirectional"))
    )
    (net (code "66") (name "Net-(U7-OUT)") (class "Default")
      (node (ref "R100") (pin "1") (pinfunction "1_1") (pintype "passive"))
      (node (ref "U7") (pin "3") (pinfunction "OUT_3") (pintype "output"))
    )
    (net (code "67") (name "VCC3V3") (class "Default")
      (node (ref "C200") (pin "2") (pinfunction "2_2") (pintype "passive"))
      (node (ref "C201") (pin "1") (pinfunction "1_1") (pintype "passive"))
      (node (ref "P1") (pin "3") (pinfunction "3_3") (pintype "passive"))
      (node (ref "P2") (pin "3") (pinfunction "3_3") (pintype "passive"))
      (node (ref "R66") (pin "1") (pinfunction "1_1") (pintype "passive"))
      (node (ref "R67") (pin "2") (pinfunction "2_2") (pintype "passive"))
      (node (ref "R68") (pin "2") (pinfunction "2_2") (pintype "passive"))
      (node (ref "R75") (pin "1") (pinfunction "1_1") (pintype "passive"))
      (node (ref "R80") (pin "1") (pinfunction "1_1") (pintype "passive"))
      (node (ref "R81") (pin "1") (pinfunction "1_1") (pintype "passive"))
      (node (ref "R82") (pin "1") (pinfunction "1_1") (pintype "passive"))
      (node (ref "R90") (pin "1") (pinfunction "1_1") (pintype "passive"))
      (node (ref "U7") (pin "4") (pinfunction "VCC_4") (pintype "power_in"))
    )
    (net (code "68") (name "unconnected-(U6A-CLK_OUT-Pad87)") (class "Default")
      (node (ref "U6") (pin "87") (pinfunction "CLK_OUT_87") (pintype "output+no_connect"))
    )
    (net (code "69") (name "unconnected-(U6A-CLK_TO_MAC-Pad85)") (class "Default")
      (node (ref "U6") (pin "85") (pinfunction "CLK_TO_MAC_85") (pintype "output+no_connect"))
    )
    (net (code "70") (name "unconnected-(U6A-COL-Pad39)") (class "Default")
      (node (ref "U6") (pin "39") (pinfunction "COL_39") (pintype "output+no_connect"))
    )
    (net (code "71") (name "unconnected-(U6A-RESERVED-Pad2)") (class "Default")
      (node (ref "U6") (pin "2") (pinfunction "RESERVED_2") (pintype "passive+no_connect"))
    )
    (net (code "72") (name "unconnected-(U6A-RESERVED-Pad23)") (class "Default")
      (node (ref "U6") (pin "23") (pinfunction "RESERVED_23") (pintype "passive+no_connect"))
    )
    (net (code "73") (name "unconnected-(U6A-RESERVED-Pad84)") (class "Default")
      (node (ref "U6") (pin "84") (pinfunction "RESERVED_84") (pintype "passive+no_connect"))
    )
    (net (code "74") (name "unconnected-(U6A-RXD4-Pad50)") (class "Default")
      (node (ref "U6") (pin "50") (pinfunction "RXD4_50") (pintype "output+no_connect"))
    )
    (net (code "75") (name "unconnected-(U6A-RXD5-Pad47)") (class "Default")
      (node (ref "U6") (pin "47") (pinfunction "RXD5_47") (pintype "output+no_connect"))
    )
    (net (code "76") (name "unconnected-(U6A-RXD6-Pad46)") (class "Default")
      (node (ref "U6") (pin "46") (pinfunction "RXD6_46") (pintype "output+no_connect"))
    )
    (net (code "77") (name "unconnected-(U6A-RXD7-Pad45)") (class "Default")
      (node (ref "U6") (pin "45") (pinfunction "RXD7_45") (pintype "output+no_connect"))
    )
    (net (code "78") (name "unconnected-(U6A-RX_CLK-Pad57)") (class "Default")
      (node (ref "U6") (pin "57") (pinfunction "RX_CLK_57") (pintype "output+no_connect"))
    )
    (net (code "79") (name "unconnected-(U6A-TDO-Pad28)") (class "Default")
      (node (ref "U6") (pin "28") (pinfunction "TDO_28") (pintype "output+no_connect"))
    )
    (net (code "80") (name "unconnected-(U7-E{slash}D_NC-Pad1)") (class "Default")
      (node (ref "U7") (pin "1") (pinfunction "E/D_NC_1") (pintype "passive+no_connect"))
    )
  )
)
